# MotorDriver-rev0.net
KiCad netlist of a schematic drawn in EAGLE
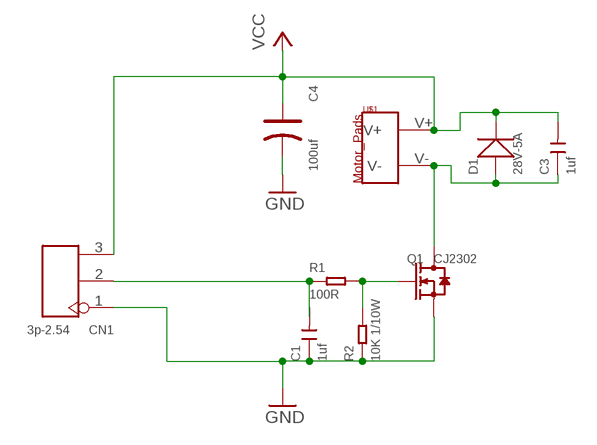
[diagram p0: schematic, sheet 1]

(export (version "E")
  (design (tool "Eeschema 10.0.6"))
  (components
    (comp (ref "C1")
      (value "1uf")
      (footprint "eagle-import:C0402")
      (fields (field (name "MPN") "CC0402KRX5R6BB105"))
      (libsource (lib "eagle-import") (part "CERAMIC-1UF-10V-10%-X5R(0402)"))
    )
    (comp (ref "C3")
      (value "1uf")
      (footprint "eagle-import:C0603")
      (fields (field (name "MPN") "CC0603KRX7R8BB105"))
      (libsource (lib "eagle-import") (part "CERAMIC-1UF-25V-10%-X7R(0603)"))
    )
    (comp (ref "C4")
      (value "100uf")
      (footprint "eagle-import:AVX-B")
      (fields (field (name "MPN") "TAJB107M010#NJ"))
      (libsource (lib "eagle-import") (part "TANTALUM-SMD-100UF-10V(AVX-B)"))
    )
    (comp (ref "CN1")
      (value "3p-2.54")
      (footprint "eagle-import:H3-2.54")
      (libsource (lib "eagle-import") (part "DIP-BLACK-MALE-HEADER-VERT(3P-2.54)"))
    )
    (comp (ref "D1")
      (value "28V-5A")
      (footprint "eagle-import:DO-214AA")
      (fields (field (name "MPN") "SS54B"))
      (libsource (lib "eagle-import") (part "SMD-DIODE-SCHOTTKY-28V-5A(DO-214AA)"))
    )
    (comp (ref "Q1")
      (value "CJ2302")
      (footprint "eagle-import:SOT-23")
      (libsource (lib "eagle-import") (part "SMD-MOSFET-N-CH-20V-2.1A-CJ2302(SOT-23)"))
    )
    (comp (ref "R1")
      (value "100R")
      (footprint "eagle-import:R0603")
      (fields (field (name "MPN") "RC0603JR-07100RL"))
      (libsource (lib "eagle-import") (part "SMD-RES-100R-5%-1/10W(0603)"))
    )
    (comp (ref "R2")
      (value "10K 1/10W")
      (footprint "eagle-import:R0603")
      (fields (field (name "MPN") "RC0603JR-0710KL"))
      (libsource (lib "eagle-import") (part "SMD-RES-10K-5%-1/10W(0603)"))
    )
    (comp (ref "U$1")
      (value "MOTOR_PADS")
      (footprint "eagle-import:MOTOR_PADS")
      (libsource (lib "eagle-import") (part "MOTOR_PADS"))
    )
  )
  (nets
    (net (code "1") (name "GND") (class "Default")
      (node (ref "C1") (pin "1") (pinfunction "1_1") (pintype "passive"))
      (node (ref "C4") (pin "-") (pinfunction "-_-") (pintype "passive"))
      (node (ref "CN1") (pin "1") (pinfunction "P$1_1") (pintype "bidirectional"))
      (node (ref "Q1") (pin "2") (pinfunction "S_2") (pintype "passive"))
      (node (ref "R2") (pin "1") (pinfunction "1_1") (pintype "passive"))
    )
    (net (code "2") (name "Net-(CN1-P$2)") (class "Default")
      (node (ref "CN1") (pin "2") (pinfunction "P$2_2") (pintype "bidirectional"))
      (node (ref "R1") (pin "1") (pinfunction "1_1") (pintype "passive"))
    )
    (net (code "3") (name "Net-(Q1-D)") (class "Default")
      (node (ref "C3") (pin "1") (pinfunction "1_1") (pintype "passive"))
      (node (ref "D1") (pin "+") (pinfunction "+_+") (pintype "passive"))
      (node (ref "Q1") (pin "3") (pinfunction "D_3") (pintype "passive"))
      (node (ref "U$1") (pin "V-") (pinfunction "V-_V-") (pintype "bidirectional"))
    )
    (net (code "4") (name "Net-(Q1-G)") (class "Default")
      (node (ref "Q1") (pin "1") (pinfunction "G_1") (pintype "passive"))
      (node (ref "R1") (pin "2") (pinfunction "2_2") (pintype "passive"))
      (node (ref "R2") (pin "2") (pinfunction "2_2") (pintype "passive"))
    )
    (net (code "5") (name "VCC") (class "Default")
      (node (ref "C3") (pin "2") (pinfunction "2_2") (pintype "passive"))
      (node (ref "C4") (pin "+") (pinfunction "+_+") (pintype "passive"))
      (node (ref "CN1") (pin "3") (pinfunction "P$3_3") (pintype "bidirectional"))
      (node (ref "D1") (pin "-") (pinfunction "-_-") (pintype "passive"))
      (node (ref "U$1") (pin "V+") (pinfunction "V+_V+") (pintype "bidirectional"))
    )
    (net (code "6") (name "unconnected-(C1-Pad2)") (class "Default")
      (node (ref "C1") (pin "2") (pinfunction "2_2") (pintype "passive"))
    )
  )
)
